# MAXboard_V2.net
KiCad netlist of a schematic drawn in EAGLE
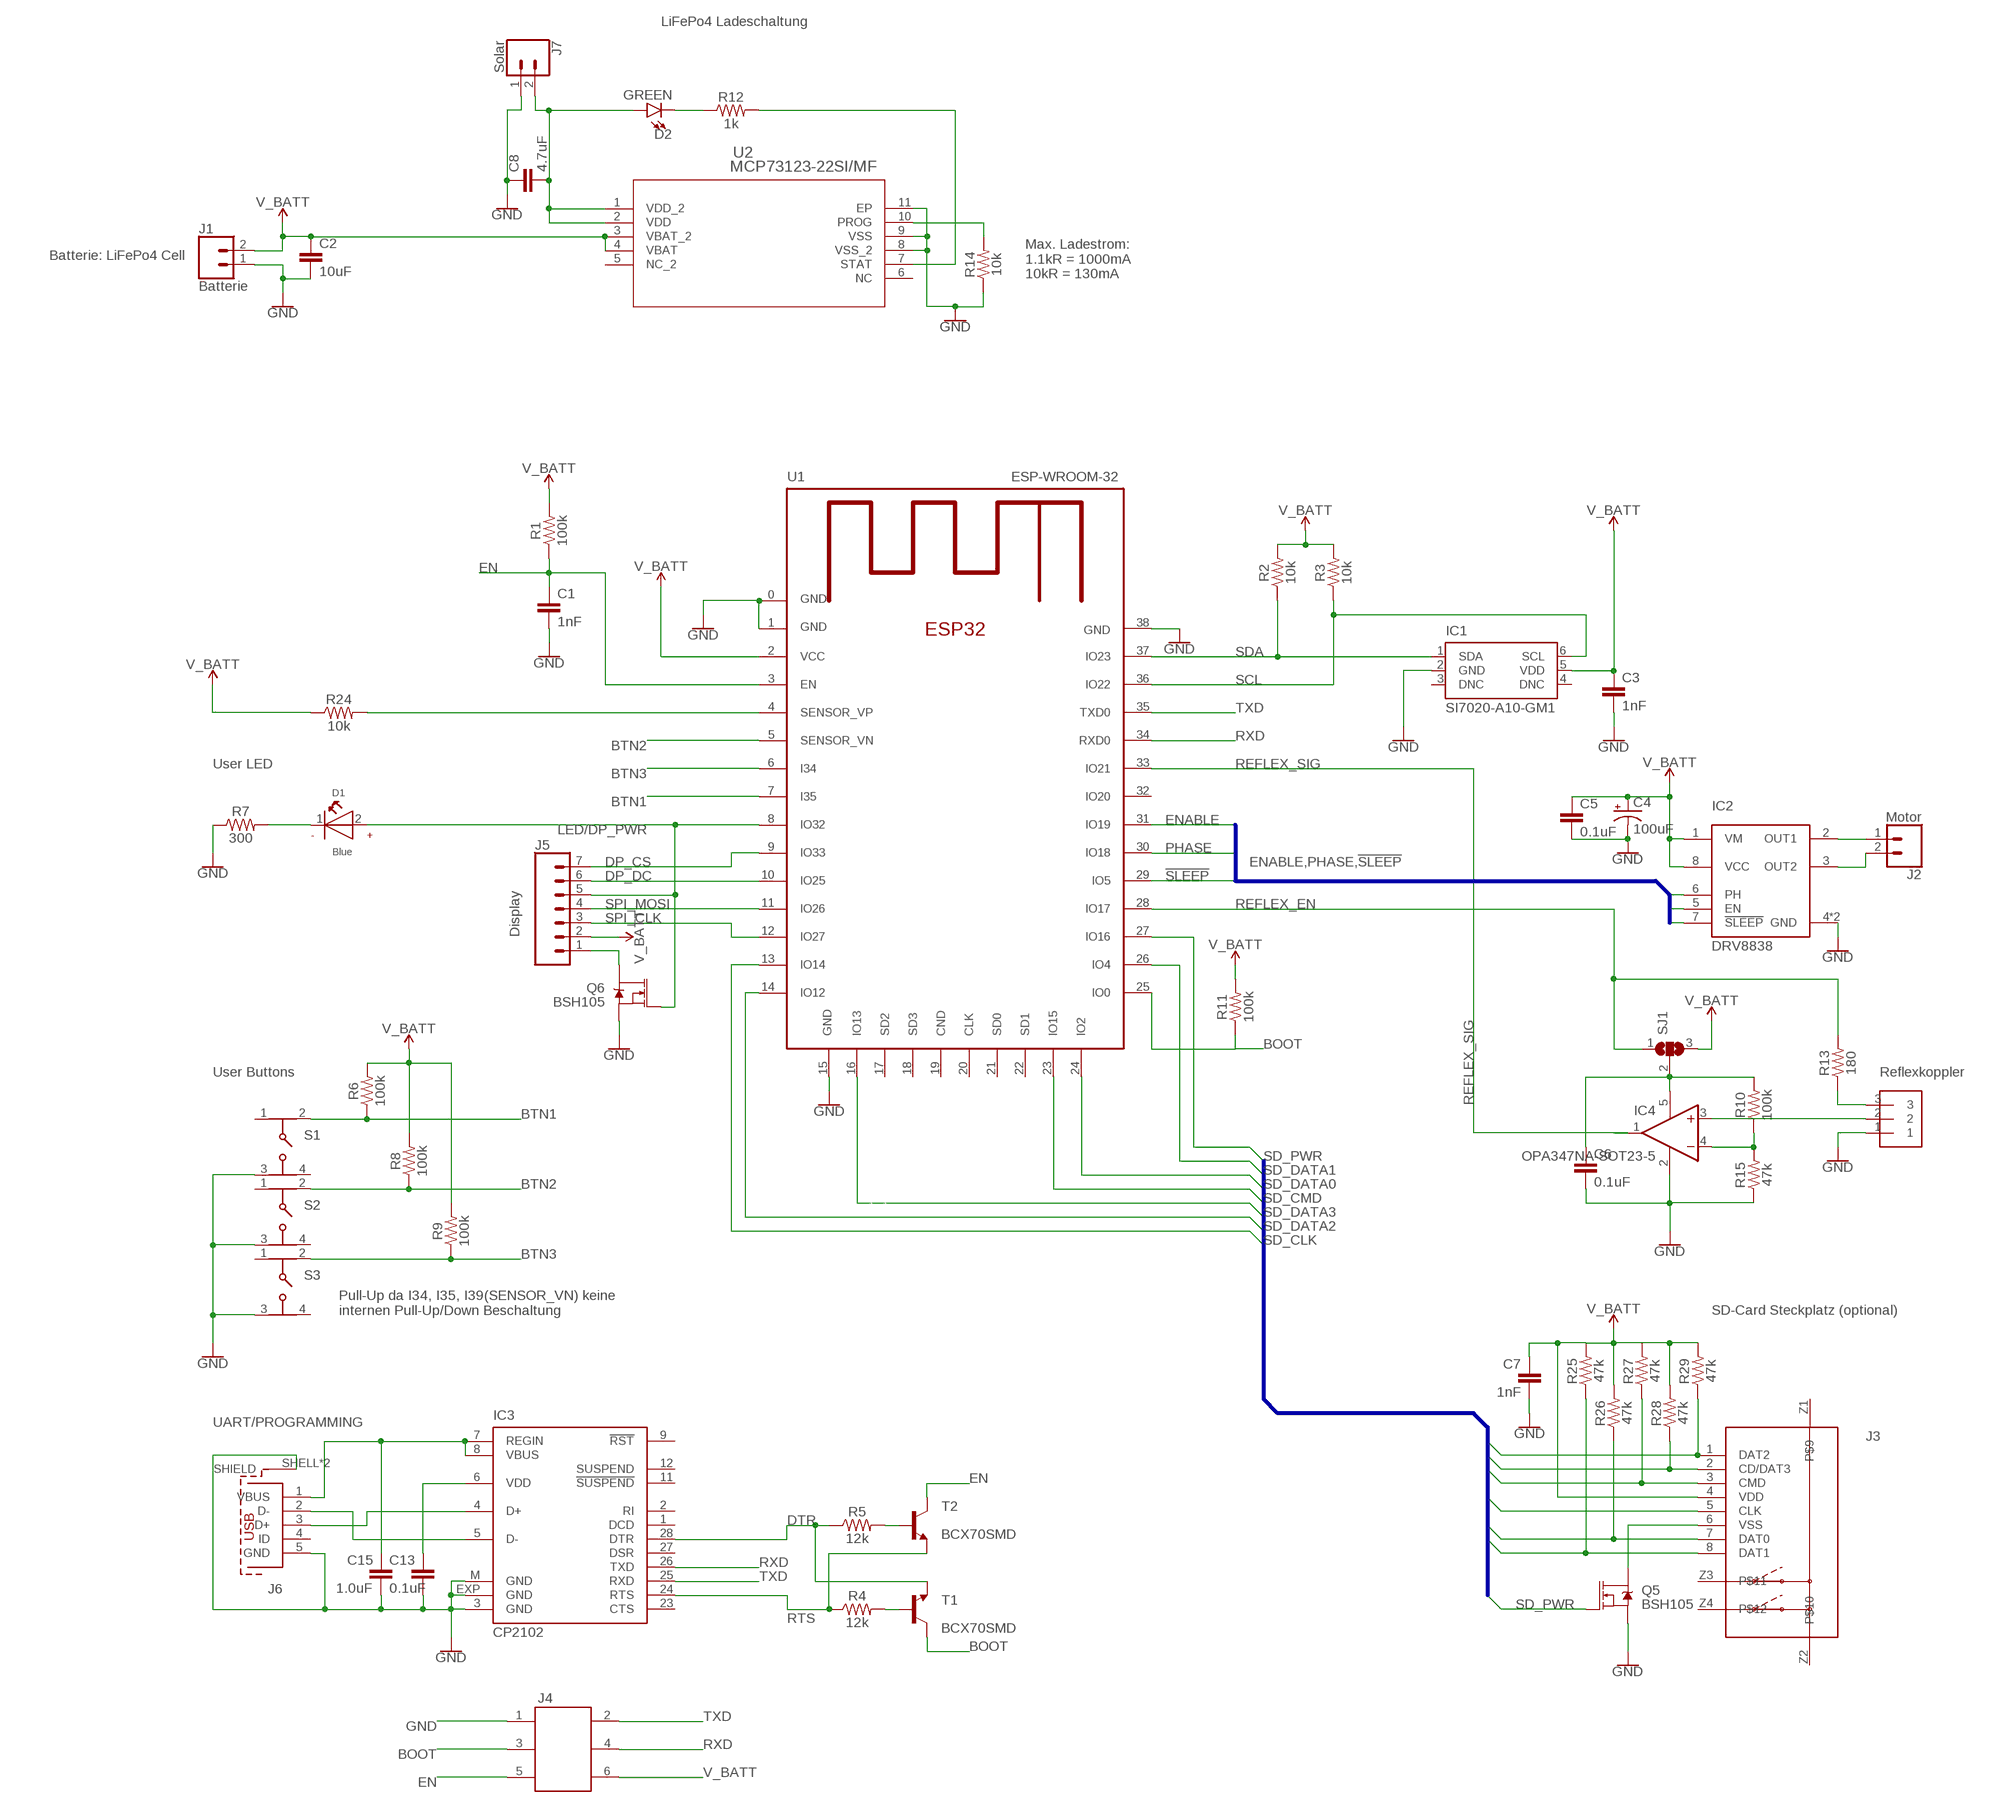
[diagram p0: schematic, sheet 1]

(export (version "E")
  (design (tool "Eeschema 10.0.6"))
  (components
    (comp (ref "C1")
      (value "1nF")
      (footprint "eagle-import:0603")
      (libsource (lib "eagle-import") (part "1.0NF/1000PF-0603-50V-10%"))
    )
    (comp (ref "C2")
      (value "10uF")
      (footprint "eagle-import:0603")
      (libsource (lib "eagle-import") (part "10UF-0603-6.3V-20%"))
    )
    (comp (ref "C3")
      (value "1nF")
      (footprint "eagle-import:0603")
      (libsource (lib "eagle-import") (part "1.0NF/1000PF-0603-50V-10%"))
    )
    (comp (ref "C4")
      (value "100uF")
      (footprint "eagle-import:PANASONIC_D")
      (libsource (lib "eagle-import") (part "100UF-POLAR-25V-20%(ELEC)"))
    )
    (comp (ref "C5")
      (value "0.1uF")
      (footprint "eagle-import:0603")
      (libsource (lib "eagle-import") (part "0.1UF-0603-25V-(+80/-20%)"))
    )
    (comp (ref "C6")
      (value "0.1uF")
      (footprint "eagle-import:0603")
      (libsource (lib "eagle-import") (part "0.1UF-0603-25V-(+80/-20%)"))
    )
    (comp (ref "C7")
      (value "1nF")
      (footprint "eagle-import:0603")
      (libsource (lib "eagle-import") (part "1.0NF/1000PF-0603-50V-10%"))
    )
    (comp (ref "C8")
      (value "4.7uF")
      (footprint "eagle-import:0603")
      (libsource (lib "eagle-import") (part "4.7UF0603"))
    )
    (comp (ref "C13")
      (value "0.1uF")
      (footprint "eagle-import:0603")
      (libsource (lib "eagle-import") (part "0.1UF-0603-25V-5%"))
    )
    (comp (ref "C15")
      (value "1.0uF")
      (footprint "eagle-import:0603")
      (libsource (lib "eagle-import") (part "1.0UF-0603-16V-10%"))
    )
    (comp (ref "D1")
      (value "Blue")
      (footprint "eagle-import:WL-SMCW_0603")
      (fields
        (field (name "MANUFACTURER") "Würth Elektronik eiSos GmbH")
        (field (name "CREATED-BY") "Christin Otto")
      )
      (libsource (lib "eagle-import") (part "WL-SMCW-150060BS75000-B"))
    )
    (comp (ref "D2")
      (value "GREEN")
      (footprint "eagle-import:LED-0603")
      (libsource (lib "eagle-import") (part "LED-GREEN0603"))
    )
    (comp (ref "IC1")
      (value "SI7020-A10-GM1")
      (footprint "eagle-import:DFN6-3X3")
      (fields (field (name "MF") "Silicon Labs") (field (name "MPN") "Si7020-GM1"))
      (libsource (lib "eagle-import") (part "SI7020-A10-GM1"))
    )
    (comp (ref "IC2")
      (value "DRV8838")
      (footprint "eagle-import:WSON8-2X2")
      (libsource (lib "eagle-import") (part "DRV8838"))
    )
    (comp (ref "IC3")
      (value "CP2102")
      (footprint "eagle-import:MLP28")
      (fields (field (name "MF") "FARNELL") (field (name "MPN") "CP2102-GM"))
      (libsource (lib "eagle-import") (part "CP2102"))
    )
    (comp (ref "IC4")
      (value "OPA347NA-SOT23-5")
      (footprint "eagle-import:SOT23-5")
      (libsource (lib "eagle-import") (part "OPA-SOT23344N"))
    )
    (comp (ref "J1")
      (value "Batterie")
      (footprint "eagle-import:1X02")
      (libsource (lib "eagle-import") (part "CONN_02"))
    )
    (comp (ref "J2")
      (value "Motor")
      (footprint "eagle-import:1X02")
      (libsource (lib "eagle-import") (part "CONN_02"))
    )
    (comp (ref "J3")
      (value "693072010801")
      (footprint "eagle-import:693072010801")
      (libsource (lib "eagle-import") (part "693072010801"))
    )
    (comp (ref "J4")
      (value "490107670612")
      (footprint "eagle-import:490107670612")
      (libsource (lib "eagle-import") (part "490107670612"))
    )
    (comp (ref "J5")
      (value "Display")
      (footprint "eagle-import:1X07")
      (libsource (lib "eagle-import") (part "CONN_07"))
    )
    (comp (ref "J6")
      (value "614105150721")
      (footprint "eagle-import:614105150721")
      (libsource (lib "eagle-import") (part "614105150721"))
    )
    (comp (ref "J7")
      (value "Solar")
      (footprint "eagle-import:1X02")
      (libsource (lib "eagle-import") (part "CONN_02"))
    )
    (comp (ref "Q5")
      (value "BSH105")
      (footprint "eagle-import:SOT23-3")
      (libsource (lib "eagle-import") (part "MOSFET-NCH-AO3404A"))
    )
    (comp (ref "Q6")
      (value "BSH105")
      (footprint "eagle-import:SOT23-3")
      (libsource (lib "eagle-import") (part "MOSFET-NCH-AO3404A"))
    )
    (comp (ref "R1")
      (value "100k")
      (footprint "eagle-import:0603")
      (libsource (lib "eagle-import") (part "100KOHM-0603-1/10W-1%"))
    )
    (comp (ref "R2")
      (value "10k")
      (footprint "eagle-import:0603")
      (libsource (lib "eagle-import") (part "10KOHM-0603-1/10W-1%"))
    )
    (comp (ref "R3")
      (value "10k")
      (footprint "eagle-import:0603")
      (libsource (lib "eagle-import") (part "10KOHM-0603-1/10W-1%"))
    )
    (comp (ref "R4")
      (value "12k")
      (footprint "eagle-import:0603")
      (libsource (lib "eagle-import") (part "12KOHM-0603-1/10W-1%"))
    )
    (comp (ref "R5")
      (value "12k")
      (footprint "eagle-import:0603")
      (libsource (lib "eagle-import") (part "12KOHM-0603-1/10W-1%"))
    )
    (comp (ref "R6")
      (value "100k")
      (footprint "eagle-import:0603")
      (libsource (lib "eagle-import") (part "100KOHM-0603-1/10W-1%"))
    )
    (comp (ref "R7")
      (value "300")
      (footprint "eagle-import:0603")
      (libsource (lib "eagle-import") (part "300OHM-0603-1/10W-1%"))
    )
    (comp (ref "R8")
      (value "100k")
      (footprint "eagle-import:0603")
      (libsource (lib "eagle-import") (part "100KOHM-0603-1/10W-1%"))
    )
    (comp (ref "R9")
      (value "100k")
      (footprint "eagle-import:0603")
      (libsource (lib "eagle-import") (part "100KOHM-0603-1/10W-1%"))
    )
    (comp (ref "R10")
      (value "100k")
      (footprint "eagle-import:0603")
      (libsource (lib "eagle-import") (part "100KOHM-0603-1/10W-1%"))
    )
    (comp (ref "R11")
      (value "100k")
      (footprint "eagle-import:0603")
      (libsource (lib "eagle-import") (part "100KOHM-0603-1/10W-1%"))
    )
    (comp (ref "R12")
      (value "1k")
      (footprint "eagle-import:0603")
      (libsource (lib "eagle-import") (part "1KOHM-0603-1/10W-1%"))
    )
    (comp (ref "R13")
      (value "180")
      (footprint "eagle-import:0603")
      (libsource (lib "eagle-import") (part "10OHM-0603-1/10W-1%"))
    )
    (comp (ref "R14")
      (value "10k")
      (footprint "eagle-import:0603")
      (libsource (lib "eagle-import") (part "10KOHM-0603-1/10W-1%"))
    )
    (comp (ref "R15")
      (value "47k")
      (footprint "eagle-import:0603")
      (libsource (lib "eagle-import") (part "47KOHM-0603-1/10W-1%"))
    )
    (comp (ref "R24")
      (value "10k")
      (footprint "eagle-import:0603")
      (libsource (lib "eagle-import") (part "10KOHM-0603-1/10W-1%"))
    )
    (comp (ref "R25")
      (value "47k")
      (footprint "eagle-import:0603")
      (libsource (lib "eagle-import") (part "47KOHM-0603-1/10W-1%"))
    )
    (comp (ref "R26")
      (value "47k")
      (footprint "eagle-import:0603")
      (libsource (lib "eagle-import") (part "47KOHM-0603-1/10W-1%"))
    )
    (comp (ref "R27")
      (value "47k")
      (footprint "eagle-import:0603")
      (libsource (lib "eagle-import") (part "47KOHM-0603-1/10W-1%"))
    )
    (comp (ref "R28")
      (value "47k")
      (footprint "eagle-import:0603")
      (libsource (lib "eagle-import") (part "47KOHM-0603-1/10W-1%"))
    )
    (comp (ref "R29")
      (value "47k")
      (footprint "eagle-import:0603")
      (libsource (lib "eagle-import") (part "47KOHM-0603-1/10W-1%"))
    )
    (comp (ref "S1")
      (value "430181038816")
      (footprint "eagle-import:430181038816")
      (libsource (lib "eagle-import") (part "430181038816"))
    )
    (comp (ref "S2")
      (value "430181038816")
      (footprint "eagle-import:430181038816")
      (libsource (lib "eagle-import") (part "430181038816"))
    )
    (comp (ref "S3")
      (value "430181038816")
      (footprint "eagle-import:430181038816")
      (libsource (lib "eagle-import") (part "430181038816"))
    )
    (comp (ref "SJ1")
      (value "SJ2W")
      (footprint "eagle-import:SJ_2")
      (libsource (lib "eagle-import") (part "SJ2W"))
    )
    (comp (ref "T1")
      (value "BCX70SMD")
      (footprint "eagle-import:SOT23")
      (libsource (lib "eagle-import") (part "BCX70SMD"))
    )
    (comp (ref "T2")
      (value "BCX70SMD")
      (footprint "eagle-import:SOT23")
      (libsource (lib "eagle-import") (part "BCX70SMD"))
    )
    (comp (ref "U$1")
      (value "SMD_3")
      (footprint "eagle-import:SMD_3X1.28")
      (libsource (lib "eagle-import") (part "SMD_3"))
    )
    (comp (ref "U1")
      (value "ESP-WROOM-32")
      (footprint "eagle-import:ESP32MOD")
      (libsource (lib "eagle-import") (part "ESP32MOD"))
    )
    (comp (ref "U2")
      (value "MCP73123-22SI/MF")
      (footprint "eagle-import:DFN10_3X3MC")
      (fields (field (name "MANUFACTURER_PART_NUMBER") "MCP7312322SIMF"))
      (libsource (lib "eagle-import") (part "MCP73123-22SI/MF"))
    )
  )
  (nets
    (net (code "1") (name "/BOOT") (class "Default")
      (node (ref "J4") (pin "3") (pinfunction "3_3") (pintype "passive"))
      (node (ref "R11") (pin "1") (pinfunction "1_1") (pintype "passive"))
      (node (ref "T1") (pin "3") (pinfunction "C_3") (pintype "passive"))
      (node (ref "U1") (pin "25") (pinfunction "IO0_25") (pintype "bidirectional"))
    )
    (net (code "2") (name "/BTN1") (class "Default")
      (node (ref "R6") (pin "1") (pinfunction "1_1") (pintype "passive"))
      (node (ref "S1") (pin "2") (pinfunction "3_2") (pintype "passive"))
      (node (ref "U1") (pin "7") (pinfunction "I35_7") (pintype "bidirectional"))
    )
    (net (code "3") (name "/BTN2") (class "Default")
      (node (ref "R8") (pin "1") (pinfunction "1_1") (pintype "passive"))
      (node (ref "S2") (pin "2") (pinfunction "3_2") (pintype "passive"))
      (node (ref "U1") (pin "5") (pinfunction "SENSOR_VN_5") (pintype "bidirectional"))
    )
    (net (code "4") (name "/BTN3") (class "Default")
      (node (ref "R9") (pin "1") (pinfunction "1_1") (pintype "passive"))
      (node (ref "S3") (pin "2") (pinfunction "3_2") (pintype "passive"))
      (node (ref "U1") (pin "6") (pinfunction "I34_6") (pintype "bidirectional"))
    )
    (net (code "5") (name "/DP_CS") (class "Default")
      (node (ref "J5") (pin "7") (pinfunction "7_7") (pintype "passive"))
      (node (ref "U1") (pin "9") (pinfunction "IO33_9") (pintype "bidirectional"))
    )
    (net (code "6") (name "/DP_DC") (class "Default")
      (node (ref "J5") (pin "6") (pinfunction "6_6") (pintype "passive"))
      (node (ref "U1") (pin "10") (pinfunction "IO25_10") (pintype "bidirectional"))
    )
    (net (code "7") (name "/DTR") (class "Default")
      (node (ref "IC3") (pin "28") (pinfunction "DTR_28") (pintype "output"))
      (node (ref "R5") (pin "1") (pinfunction "1_1") (pintype "passive"))
      (node (ref "T1") (pin "2") (pinfunction "E_2") (pintype "passive"))
    )
    (net (code "8") (name "/EN") (class "Default")
      (node (ref "C1") (pin "1") (pinfunction "1_1") (pintype "passive"))
      (node (ref "J4") (pin "5") (pinfunction "5_5") (pintype "passive"))
      (node (ref "R1") (pin "1") (pinfunction "1_1") (pintype "passive"))
      (node (ref "T2") (pin "3") (pinfunction "C_3") (pintype "passive"))
      (node (ref "U1") (pin "3") (pinfunction "EN_3") (pintype "bidirectional"))
    )
    (net (code "9") (name "/ENABLE") (class "Default")
      (node (ref "IC2") (pin "5") (pinfunction "EN_5") (pintype "bidirectional"))
      (node (ref "U1") (pin "31") (pinfunction "IO19_31") (pintype "bidirectional"))
    )
    (net (code "10") (name "/LED{slash}DP_PWR") (class "Default")
      (node (ref "D1") (pin "2") (pinfunction "+_2") (pintype "bidirectional"))
      (node (ref "J5") (pin "5") (pinfunction "5_5") (pintype "passive"))
      (node (ref "Q6") (pin "1") (pinfunction "G_1") (pintype "bidirectional"))
      (node (ref "U1") (pin "8") (pinfunction "IO32_8") (pintype "bidirectional"))
    )
    (net (code "11") (name "/PHASE") (class "Default")
      (node (ref "IC2") (pin "6") (pinfunction "PH_6") (pintype "bidirectional"))
      (node (ref "U1") (pin "30") (pinfunction "IO18_30") (pintype "bidirectional"))
    )
    (net (code "12") (name "/REFLEX_EN") (class "Default")
      (node (ref "R13") (pin "2") (pinfunction "2_2") (pintype "passive"))
      (node (ref "SJ1") (pin "1") (pinfunction "1_1") (pintype "passive"))
      (node (ref "U1") (pin "28") (pinfunction "IO17_28") (pintype "bidirectional"))
    )
    (net (code "13") (name "/REFLEX_SIG") (class "Default")
      (node (ref "IC4") (pin "1") (pinfunction "OUT_1") (pintype "output"))
      (node (ref "U1") (pin "33") (pinfunction "IO21_33") (pintype "bidirectional"))
    )
    (net (code "14") (name "/RTS") (class "Default")
      (node (ref "IC3") (pin "24") (pinfunction "RTS_24") (pintype "output"))
      (node (ref "R4") (pin "1") (pinfunction "1_1") (pintype "passive"))
      (node (ref "T2") (pin "2") (pinfunction "E_2") (pintype "passive"))
    )
    (net (code "15") (name "/RXD") (class "Default")
      (node (ref "IC3") (pin "26") (pinfunction "TXD_26") (pintype "output"))
      (node (ref "J4") (pin "4") (pinfunction "4_4") (pintype "passive"))
      (node (ref "U1") (pin "34") (pinfunction "RXD0_34") (pintype "bidirectional"))
    )
    (net (code "16") (name "/SCL") (class "Default")
      (node (ref "IC1") (pin "6") (pinfunction "SCL_6") (pintype "input"))
      (node (ref "R3") (pin "1") (pinfunction "1_1") (pintype "passive"))
      (node (ref "U1") (pin "36") (pinfunction "IO22_36") (pintype "bidirectional"))
    )
    (net (code "17") (name "/SDA") (class "Default")
      (node (ref "IC1") (pin "1") (pinfunction "SDA_1") (pintype "bidirectional"))
      (node (ref "R2") (pin "1") (pinfunction "1_1") (pintype "passive"))
      (node (ref "U1") (pin "37") (pinfunction "IO23_37") (pintype "bidirectional"))
    )
    (net (code "18") (name "/SD_CLK") (class "Default")
      (node (ref "J3") (pin "5") (pinfunction "CLK_5") (pintype "bidirectional"))
      (node (ref "U1") (pin "13") (pinfunction "IO14_13") (pintype "bidirectional"))
    )
    (net (code "19") (name "/SD_CMD") (class "Default")
      (node (ref "J3") (pin "3") (pinfunction "CMD_3") (pintype "bidirectional"))
      (node (ref "R27") (pin "1") (pinfunction "1_1") (pintype "passive"))
      (node (ref "U1") (pin "23") (pinfunction "IO15_23") (pintype "bidirectional"))
    )
    (net (code "20") (name "/SD_DATA0") (class "Default")
      (node (ref "J3") (pin "7") (pinfunction "DAT0_7") (pintype "bidirectional"))
      (node (ref "R26") (pin "1") (pinfunction "1_1") (pintype "passive"))
      (node (ref "U1") (pin "24") (pinfunction "IO2_24") (pintype "bidirectional"))
    )
    (net (code "21") (name "/SD_DATA1") (class "Default")
      (node (ref "J3") (pin "8") (pinfunction "DAT1_8") (pintype "bidirectional"))
      (node (ref "R25") (pin "1") (pinfunction "1_1") (pintype "passive"))
      (node (ref "U1") (pin "26") (pinfunction "IO4_26") (pintype "bidirectional"))
    )
    (net (code "22") (name "/SD_DATA2") (class "Default")
      (node (ref "J3") (pin "1") (pinfunction "DAT2_1") (pintype "bidirectional"))
      (node (ref "R29") (pin "1") (pinfunction "1_1") (pintype "passive"))
      (node (ref "U1") (pin "14") (pinfunction "IO12_14") (pintype "bidirectional"))
    )
    (net (code "23") (name "/SD_DATA3") (class "Default")
      (node (ref "J3") (pin "2") (pinfunction "CD/DAT3_2") (pintype "bidirectional"))
      (node (ref "R28") (pin "1") (pinfunction "1_1") (pintype "passive"))
    )
    (net (code "24") (name "/SD_PWR") (class "Default")
      (node (ref "Q5") (pin "1") (pinfunction "G_1") (pintype "bidirectional"))
      (node (ref "U1") (pin "27") (pinfunction "IO16_27") (pintype "bidirectional"))
    )
    (net (code "25") (name "/SPI_CLK") (class "Default")
      (node (ref "J5") (pin "3") (pinfunction "3_3") (pintype "passive"))
      (node (ref "U1") (pin "12") (pinfunction "IO27_12") (pintype "bidirectional"))
    )
    (net (code "26") (name "/SPI_MOSI") (class "Default")
      (node (ref "J5") (pin "4") (pinfunction "4_4") (pintype "passive"))
      (node (ref "U1") (pin "11") (pinfunction "IO26_11") (pintype "bidirectional"))
    )
    (net (code "27") (name "/TXD") (class "Default")
      (node (ref "IC3") (pin "25") (pinfunction "RXD_25") (pintype "input"))
      (node (ref "J4") (pin "2") (pinfunction "2_2") (pintype "passive"))
      (node (ref "U1") (pin "35") (pinfunction "TXD0_35") (pintype "bidirectional"))
    )
    (net (code "29") (name "/~{SLEEP}") (class "Default")
      (node (ref "IC2") (pin "7") (pinfunction "~{SLEEP}_7") (pintype "bidirectional"))
      (node (ref "U1") (pin "29") (pinfunction "IO5_29") (pintype "bidirectional"))
    )
    (net (code "30") (name "GND") (class "Default")
      (node (ref "C1") (pin "2") (pinfunction "2_2") (pintype "passive"))
      (node (ref "C13") (pin "2") (pinfunction "2_2") (pintype "passive"))
      (node (ref "C15") (pin "2") (pinfunction "2_2") (pintype "passive"))
      (node (ref "C2") (pin "2") (pinfunction "2_2") (pintype "passive"))
      (node (ref "C3") (pin "2") (pinfunction "2_2") (pintype "passive"))
      (node (ref "C4") (pin "-") (pinfunction "-_-") (pintype "passive"))
      (node (ref "C5") (pin "2") (pinfunction "2_2") (pintype "passive"))
      (node (ref "C6") (pin "2") (pinfunction "2_2") (pintype "passive"))
      (node (ref "C7") (pin "2") (pinfunction "2_2") (pintype "passive"))
      (node (ref "C8") (pin "1") (pinfunction "1_1") (pintype "passive"))
      (node (ref "IC1") (pin "2") (pinfunction "GND_2") (pintype "power_in"))
      (node (ref "IC2") (pin "4") (pinfunction "GND_4") (pintype "bidirectional"))
      (node (ref "IC2") (pin "EXP") (pinfunction "GND_EXP") (pintype "bidirectional"))
      (node (ref "IC3") (pin "3") (pinfunction "GND_3") (pintype "power_in"))
      (node (ref "IC3") (pin "EXP") (pinfunction "GND_EXP") (pintype "power_in"))
      (node (ref "IC3") (pin "M") (pinfunction "GND_M") (pintype "power_in"))
      (node (ref "IC4") (pin "2") (pinfunction "V-_2") (pintype "power_in"))
      (node (ref "J1") (pin "1") (pinfunction "1_1") (pintype "passive"))
      (node (ref "J4") (pin "1") (pinfunction "1_1") (pintype "passive"))
      (node (ref "J6") (pin "5") (pinfunction "GND_5") (pintype "passive"))
      (node (ref "J6") (pin "SHELL") (pinfunction "SHIELD_SHELL") (pintype "passive"))
      (node (ref "J6") (pin "SHELL1") (pinfunction "SHIELD_SHELL1") (pintype "passive"))
      (node (ref "J7") (pin "1") (pinfunction "1_1") (pintype "passive"))
      (node (ref "Q5") (pin "2") (pinfunction "S_2") (pintype "bidirectional"))
      (node (ref "Q6") (pin "2") (pinfunction "S_2") (pintype "bidirectional"))
      (node (ref "R14") (pin "1") (pinfunction "1_1") (pintype "passive"))
      (node (ref "R15") (pin "1") (pinfunction "1_1") (pintype "passive"))
      (node (ref "R7") (pin "1") (pinfunction "1_1") (pintype "passive"))
      (node (ref "S1") (pin "3") (pinfunction "2_3") (pintype "passive"))
      (node (ref "S2") (pin "3") (pinfunction "2_3") (pintype "passive"))
      (node (ref "S3") (pin "3") (pinfunction "2_3") (pintype "passive"))
      (node (ref "U$1") (pin "1") (pinfunction "1_1") (pintype "bidirectional"))
      (node (ref "U1") (pin "0") (pinfunction "GND_0") (pintype "power_in"))
      (node (ref "U1") (pin "1") (pinfunction "GND_1") (pintype "power_in"))
      (node (ref "U1") (pin "15") (pinfunction "GND_15") (pintype "power_in"))
      (node (ref "U1") (pin "38") (pinfunction "GND_38") (pintype "power_in"))
      (node (ref "U2") (pin "11") (pinfunction "EP_11") (pintype "passive"))
      (node (ref "U2") (pin "8") (pinfunction "VSS_2_8") (pintype "power_in"))
      (node (ref "U2") (pin "9") (pinfunction "VSS_9") (pintype "power_in"))
    )
    (net (code "31") (name "Net-(D1--)") (class "Default")
      (node (ref "D1") (pin "1") (pinfunction "-_1") (pintype "bidirectional"))
      (node (ref "R7") (pin "2") (pinfunction "2_2") (pintype "passive"))
    )
    (net (code "32") (name "Net-(D2-PadC)") (class "Default")
      (node (ref "D2") (pin "C") (pinfunction "C_C") (pintype "passive"))
      (node (ref "R12") (pin "1") (pinfunction "1_1") (pintype "passive"))
    )
    (net (code "33") (name "Net-(IC2-OUT1)") (class "Default")
      (node (ref "IC2") (pin "2") (pinfunction "OUT1_2") (pintype "bidirectional"))
      (node (ref "J2") (pin "1") (pinfunction "1_1") (pintype "passive"))
    )
    (net (code "34") (name "Net-(IC2-OUT2)") (class "Default")
      (node (ref "IC2") (pin "3") (pinfunction "OUT2_3") (pintype "bidirectional"))
      (node (ref "J2") (pin "2") (pinfunction "2_2") (pintype "passive"))
    )
    (net (code "35") (name "Net-(IC3-D+)") (class "Default")
      (node (ref "IC3") (pin "4") (pinfunction "D+_4") (pintype "bidirectional"))
      (node (ref "J6") (pin "3") (pinfunction "D+_3") (pintype "passive"))
    )
    (net (code "36") (name "Net-(IC3-D-)") (class "Default")
      (node (ref "IC3") (pin "5") (pinfunction "D-_5") (pintype "bidirectional"))
      (node (ref "J6") (pin "2") (pinfunction "D-_2") (pintype "passive"))
    )
    (net (code "37") (name "Net-(IC3-REGIN)") (class "Default")
      (node (ref "C15") (pin "1") (pinfunction "1_1") (pintype "passive"))
      (node (ref "IC3") (pin "7") (pinfunction "REGIN_7") (pintype "passive"))
      (node (ref "IC3") (pin "8") (pinfunction "VBUS_8") (pintype "input"))
      (node (ref "J6") (pin "1") (pinfunction "VBUS_1") (pintype "passive"))
    )
    (net (code "38") (name "Net-(IC3-VDD)") (class "Default")
      (node (ref "C13") (pin "1") (pinfunction "1_1") (pintype "passive"))
      (node (ref "IC3") (pin "6") (pinfunction "VDD_6") (pintype "power_in"))
    )
    (net (code "39") (name "Net-(IC4-+IN)") (class "Default")
      (node (ref "IC4") (pin "3") (pinfunction "+IN_3") (pintype "input"))
      (node (ref "U$1") (pin "2") (pinfunction "2_2") (pintype "bidirectional"))
    )
    (net (code "40") (name "Net-(IC4--IN)") (class "Default")
      (node (ref "IC4") (pin "4") (pinfunction "-IN_4") (pintype "input"))
      (node (ref "R10") (pin "1") (pinfunction "1_1") (pintype "passive"))
      (node (ref "R15") (pin "2") (pinfunction "2_2") (pintype "passive"))
    )
    (net (code "41") (name "Net-(IC4-V+)") (class "Default")
      (node (ref "C6") (pin "1") (pinfunction "1_1") (pintype "passive"))
      (node (ref "IC4") (pin "5") (pinfunction "V+_5") (pintype "power_in"))
      (node (ref "R10") (pin "2") (pinfunction "2_2") (pintype "passive"))
      (node (ref "SJ1") (pin "2") (pinfunction "2_2") (pintype "passive"))
    )
    (net (code "42") (name "Net-(J3-VSS)") (class "Default")
      (node (ref "J3") (pin "6") (pinfunction "VSS_6") (pintype "bidirectional"))
      (node (ref "Q5") (pin "3") (pinfunction "D_3") (pintype "bidirectional"))
    )
    (net (code "43") (name "Net-(Q6-D)") (class "Default")
      (node (ref "J5") (pin "1") (pinfunction "1_1") (pintype "passive"))
      (node (ref "Q6") (pin "3") (pinfunction "D_3") (pintype "bidirectional"))
    )
    (net (code "44") (name "Net-(R13-Pad1)") (class "Default")
      (node (ref "R13") (pin "1") (pinfunction "1_1") (pintype "passive"))
      (node (ref "U$1") (pin "3") (pinfunction "3_3") (pintype "bidirectional"))
    )
    (net (code "45") (name "Net-(T1-B)") (class "Default")
      (node (ref "R4") (pin "2") (pinfunction "2_2") (pintype "passive"))
      (node (ref "T1") (pin "1") (pinfunction "B_1") (pintype "passive"))
    )
    (net (code "46") (name "Net-(T2-B)") (class "Default")
      (node (ref "R5") (pin "2") (pinfunction "2_2") (pintype "passive"))
      (node (ref "T2") (pin "1") (pinfunction "B_1") (pintype "passive"))
    )
    (net (code "47") (name "Net-(U1-SENSOR_VP)") (class "Default")
      (node (ref "R24") (pin "2") (pinfunction "2_2") (pintype "passive"))
      (node (ref "U1") (pin "4") (pinfunction "SENSOR_VP_4") (pintype "bidirectional"))
    )
    (net (code "48") (name "Net-(U2-PROG)") (class "Default")
      (node (ref "R14") (pin "2") (pinfunction "2_2") (pintype "passive"))
      (node (ref "U2") (pin "10") (pinfunction "PROG_10") (pintype "passive"))
    )
    (net (code "49") (name "Net-(U2-STAT)") (class "Default")
      (node (ref "R12") (pin "2") (pinfunction "2_2") (pintype "passive"))
      (node (ref "U2") (pin "7") (pinfunction "STAT_7") (pintype "output"))
    )
    (net (code "50") (name "Net-(U2-VDD)") (class "Default")
      (node (ref "C8") (pin "2") (pinfunction "2_2") (pintype "passive"))
      (node (ref "D2") (pin "A") (pinfunction "A_A") (pintype "passive"))
      (node (ref "J7") (pin "2") (pinfunction "2_2") (pintype "passive"))
      (node (ref "U2") (pin "1") (pinfunction "VDD_2_1") (pintype "power_in"))
      (node (ref "U2") (pin "2") (pinfunction "VDD_2") (pintype "power_in"))
    )
    (net (code "51") (name "V_BATT") (class "Default")
      (node (ref "C2") (pin "1") (pinfunction "1_1") (pintype "passive"))
      (node (ref "C3") (pin "1") (pinfunction "1_1") (pintype "passive"))
      (node (ref "C4") (pin "+") (pinfunction "+_+") (pintype "passive"))
      (node (ref "C5") (pin "1") (pinfunction "1_1") (pintype "passive"))
      (node (ref "C7") (pin "1") (pinfunction "1_1") (pintype "passive"))
      (node (ref "IC1") (pin "5") (pinfunction "VDD_5") (pintype "power_in"))
      (node (ref "IC2") (pin "1") (pinfunction "VM_1") (pintype "bidirectional"))
      (node (ref "IC2") (pin "8") (pinfunction "VCC_8") (pintype "bidirectional"))
      (node (ref "J1") (pin "2") (pinfunction "2_2") (pintype "passive"))
      (node (ref "J3") (pin "4") (pinfunction "VDD_4") (pintype "bidirectional"))
      (node (ref "J4") (pin "6") (pinfunction "6_6") (pintype "passive"))
      (node (ref "J5") (pin "2") (pinfunction "2_2") (pintype "passive"))
      (node (ref "R1") (pin "2") (pinfunction "2_2") (pintype "passive"))
      (node (ref "R11") (pin "2") (pinfunction "2_2") (pintype "passive"))
      (node (ref "R2") (pin "2") (pinfunction "2_2") (pintype "passive"))
      (node (ref "R24") (pin "1") (pinfunction "1_1") (pintype "passive"))
      (node (ref "R25") (pin "2") (pinfunction "2_2") (pintype "passive"))
      (node (ref "R26") (pin "2") (pinfunction "2_2") (pintype "passive"))
      (node (ref "R27") (pin "2") (pinfunction "2_2") (pintype "passive"))
      (node (ref "R28") (pin "2") (pinfunction "2_2") (pintype "passive"))
      (node (ref "R29") (pin "2") (pinfunction "2_2") (pintype "passive"))
      (node (ref "R3") (pin "2") (pinfunction "2_2") (pintype "passive"))
      (node (ref "R6") (pin "2") (pinfunction "2_2") (pintype "passive"))
      (node (ref "R8") (pin "2") (pinfunction "2_2") (pintype "passive"))
      (node (ref "R9") (pin "2") (pinfunction "2_2") (pintype "passive"))
      (node (ref "SJ1") (pin "3") (pinfunction "3_3") (pintype "passive"))
      (node (ref "U1") (pin "2") (pinfunction "VCC_2") (pintype "power_in"))
      (node (ref "U2") (pin "3") (pinfunction "VBAT_2_3") (pintype "power_in"))
      (node (ref "U2") (pin "4") (pinfunction "VBAT_4") (pintype "power_in"))
    )
    (net (code "52") (name "unconnected-(IC1-DNC-Pad3)") (class "Default")
      (node (ref "IC1") (pin "3") (pinfunction "DNC_3") (pintype "no_connect"))
    )
    (net (code "53") (name "unconnected-(IC1-DNC-Pad4)") (class "Default")
      (node (ref "IC1") (pin "4") (pinfunction "DNC_4") (pintype "no_connect"))
    )
    (net (code "54") (name "unconnected-(IC3-CTS-Pad23)") (class "Default")
      (node (ref "IC3") (pin "23") (pinfunction "CTS_23") (pintype "input"))
    )
    (net (code "55") (name "unconnected-(IC3-DCD-Pad1)") (class "Default")
      (node (ref "IC3") (pin "1") (pinfunction "DCD_1") (pintype "input"))
    )
    (net (code "56") (name "unconnected-(IC3-DSR-Pad27)") (class "Default")
      (node (ref "IC3") (pin "27") (pinfunction "DSR_27") (pintype "input"))
    )
    (net (code "57") (name "unconnected-(IC3-RI-Pad2)") (class "Default")
      (node (ref "IC3") (pin "2") (pinfunction "RI_2") (pintype "input"))
    )
    (net (code "58") (name "unconnected-(IC3-SUSPEND-Pad12)") (class "Default")
      (node (ref "IC3") (pin "12") (pinfunction "SUSPEND_12") (pintype "output"))
    )
    (net (code "59") (name "unconnected-(IC3-~{RST}-Pad9)") (class "Default")
      (node (ref "IC3") (pin "9") (pinfunction "~{RST}_9") (pintype "bidirectional"))
    )
    (net (code "60") (name "unconnected-(IC3-~{SUSPEND}-Pad11)") (class "Default")
      (node (ref "IC3") (pin "11") (pinfunction "~{SUSPEND}_11") (pintype "output"))
    )
    (net (code "61") (name "unconnected-(J3-P$9-PadZ1)") (class "Default")
      (node (ref "J3") (pin "Z1") (pinfunction "P$9_Z1") (pintype "bidirectional"))
    )
    (net (code "62") (name "unconnected-(J3-P$10-PadZ2)") (class "Default")
      (node (ref "J3") (pin "Z2") (pinfunction "P$10_Z2") (pintype "bidirectional"))
    )
    (net (code "63") (name "unconnected-(J3-P$11-PadZ3)") (class "Default")
      (node (ref "J3") (pin "Z3") (pinfunction "P$11_Z3") (pintype "bidirectional"))
    )
    (net (code "64") (name "unconnected-(J3-P$12-PadZ4)") (class "Default")
      (node (ref "J3") (pin "Z4") (pinfunction "P$12_Z4") (pintype "bidirectional"))
    )
    (net (code "65") (name "unconnected-(J6-ID-Pad4)") (class "Default")
      (node (ref "J6") (pin "4") (pinfunction "ID_4") (pintype "passive"))
    )
    (net (code "66") (name "unconnected-(S1-Pad1)") (class "Default")
      (node (ref "S1") (pin "1") (pinfunction "1_1") (pintype "passive"))
    )
    (net (code "67") (name "unconnected-(S1-Pad4)") (class "Default")
      (node (ref "S1") (pin "4") (pinfunction "4_4") (pintype "passive"))
    )
    (net (code "68") (name "unconnected-(S2-Pad1)") (class "Default")
      (node (ref "S2") (pin "1") (pinfunction "1_1") (pintype "passive"))
    )
    (net (code "69") (name "unconnected-(S2-Pad4)") (class "Default")
      (node (ref "S2") (pin "4") (pinfunction "4_4") (pintype "passive"))
    )
    (net (code "70") (name "unconnected-(S3-Pad1)") (class "Default")
      (node (ref "S3") (pin "1") (pinfunction "1_1") (pintype "passive"))
    )
    (net (code "71") (name "unconnected-(S3-Pad4)") (class "Default")
      (node (ref "S3") (pin "4") (pinfunction "4_4") (pintype "passive"))
    )
    (net (code "72") (name "unconnected-(U1-CLK-Pad20)") (class "Default")
      (node (ref "U1") (pin "20") (pinfunction "CLK_20") (pintype "bidirectional"))
    )
    (net (code "73") (name "unconnected-(U1-CND-Pad19)") (class "Default")
      (node (ref "U1") (pin "19") (pinfunction "CND_19") (pintype "bidirectional"))
    )
    (net (code "74") (name "unconnected-(U1-IO13-Pad16)") (class "Default")
      (node (ref "U1") (pin "16") (pinfunction "IO13_16") (pintype "bidirectional"))
    )
    (net (code "75") (name "unconnected-(U1-IO20-Pad32)") (class "Default")
      (node (ref "U1") (pin "32") (pinfunction "IO20_32") (pintype "bidirectional"))
    )
    (net (code "76") (name "unconnected-(U1-SD0-Pad21)") (class "Default")
      (node (ref "U1") (pin "21") (pinfunction "SD0_21") (pintype "bidirectional"))
    )
    (net (code "77") (name "unconnected-(U1-SD1-Pad22)") (class "Default")
      (node (ref "U1") (pin "22") (pinfunction "SD1_22") (pintype "bidirectional"))
    )
    (net (code "78") (name "unconnected-(U1-SD2-Pad17)") (class "Default")
      (node (ref "U1") (pin "17") (pinfunction "SD2_17") (pintype "bidirectional"))
    )
    (net (code "79") (name "unconnected-(U1-SD3-Pad18)") (class "Default")
      (node (ref "U1") (pin "18") (pinfunction "SD3_18") (pintype "bidirectional"))
    )
    (net (code "80") (name "unconnected-(U2-NC-Pad6)") (class "Default")
      (node (ref "U2") (pin "6") (pinfunction "NC_6") (pintype "no_connect"))
    )
    (net (code "81") (name "unconnected-(U2-NC_2-Pad5)") (class "Default")
      (node (ref "U2") (pin "5") (pinfunction "NC_2_5") (pintype "no_connect"))
    )
  )
)
